# ACS_5_5.net
KiCad netlist of a schematic drawn in EAGLE
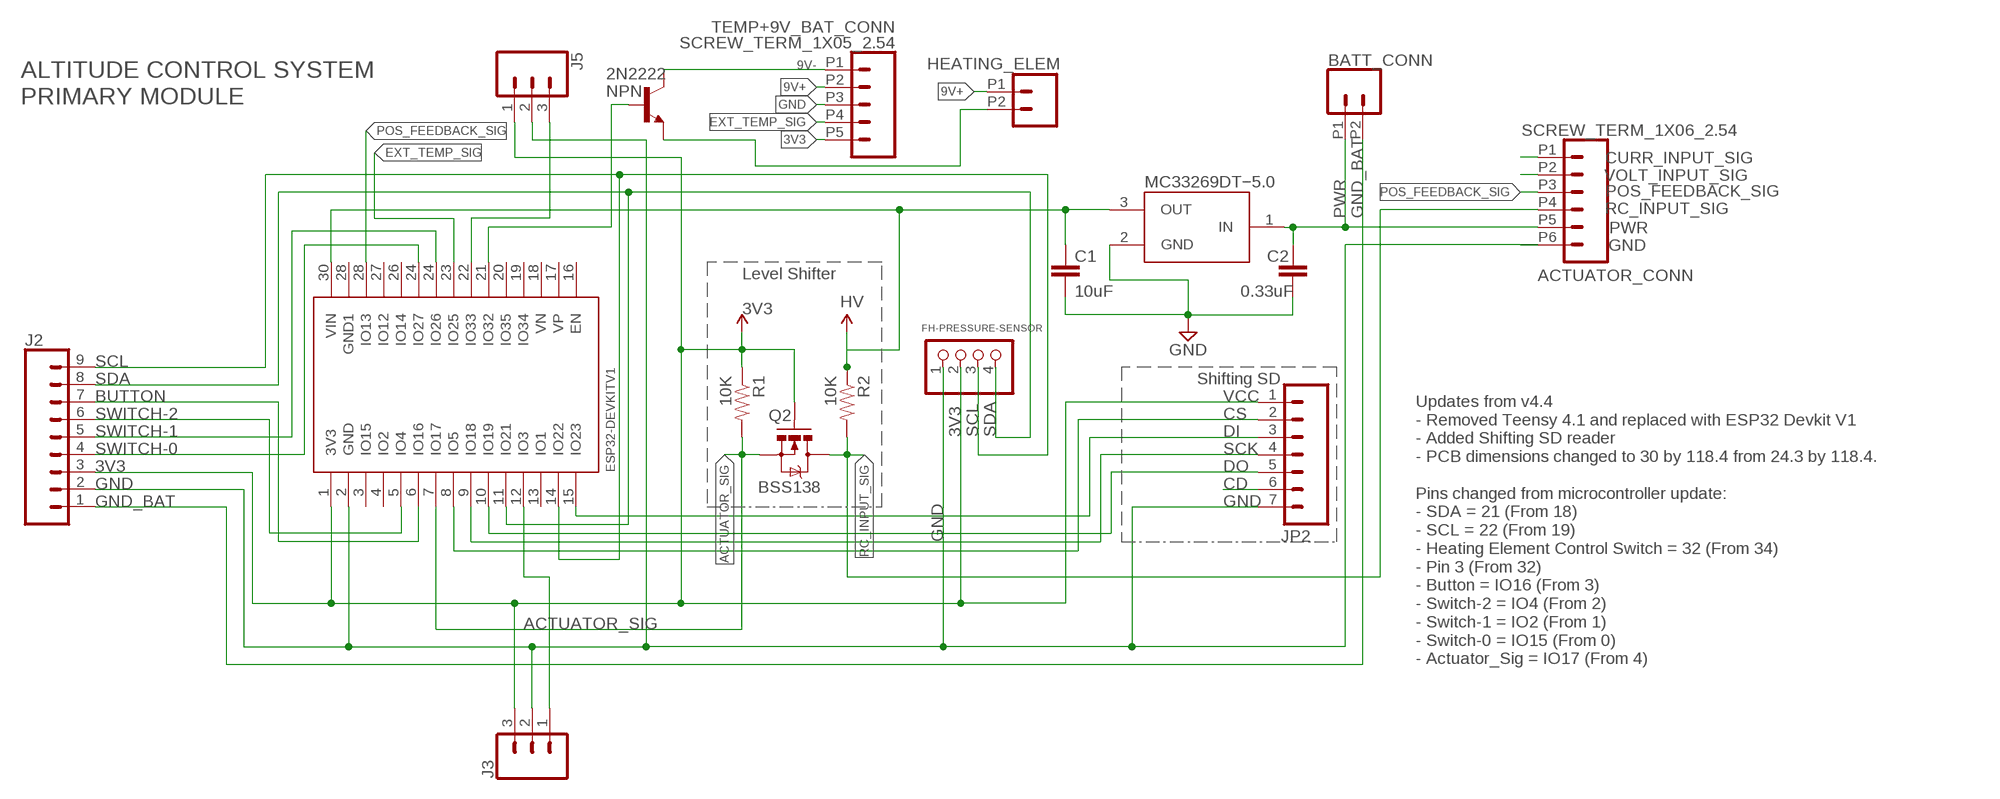
[diagram p0: schematic, sheet 1]

(export (version "E")
  (design (tool "Eeschema 10.0.6"))
  (components
    (comp (ref "2N2222")
      (value "NPN")
      (footprint "eagle-import:SOT95P237X112-3N")
      (libsource (lib "eagle-import") (part "NPNSOT23_"))
    )
    (comp (ref "ACTUATOR_CONN")
      (value "SCREW_TERM_1X06_2.54")
      (footprint "eagle-import:1X06_2.54_SCREWTERM")
      (libsource (lib "eagle-import") (part "SCREW_TERM_1X06_2.54"))
    )
    (comp (ref "BATT_CONN")
      (value "CONN_022.54MM_SCREWTERM")
      (footprint "eagle-import:1X02_2.54_SCREWTERM")
      (libsource (lib "eagle-import") (part "CONN_022.54MM_SCREWTERM"))
    )
    (comp (ref "C1")
      (value "10uF")
      (footprint "eagle-import:CAPC1608X85")
      (libsource (lib "eagle-import") (part "CCHIP-0603(1608-METRIC)_"))
    )
    (comp (ref "C2")
      (value "0.33uF")
      (footprint "eagle-import:CAPC1608X85")
      (libsource (lib "eagle-import") (part "CCHIP-0603(1608-METRIC)_"))
    )
    (comp (ref "FH-PRESSURE-SENSOR")
      (value "PINHD-1X4")
      (footprint "eagle-import:1X04")
      (libsource (lib "eagle-import") (part "PINHD-1X4"))
    )
    (comp (ref "HEATING_ELEM")
      (value "CONN_022.54MM_SCREWTERM")
      (footprint "eagle-import:1X02_2.54_SCREWTERM")
      (libsource (lib "eagle-import") (part "CONN_022.54MM_SCREWTERM"))
    )
    (comp (ref "J2")
      (value "CONN_09")
      (footprint "eagle-import:1X09")
      (libsource (lib "eagle-import") (part "CONN_09"))
    )
    (comp (ref "J3")
      (value "CONN_03")
      (footprint "eagle-import:1X03")
      (libsource (lib "eagle-import") (part "CONN_03"))
    )
    (comp (ref "J5")
      (value "CONN_03")
      (footprint "eagle-import:1X03")
      (libsource (lib "eagle-import") (part "CONN_03"))
    )
    (comp (ref "JP2")
      (value "M07")
      (footprint "eagle-import:1X07")
      (libsource (lib "eagle-import") (part "M07"))
    )
    (comp (ref "Q2")
      (value "BSS138")
      (footprint "eagle-import:SOT23-3")
      (libsource (lib "eagle-import") (part "MOSFET-NCHANNELSMD"))
    )
    (comp (ref "R1")
      (value "10K")
      (footprint "eagle-import:0603-RES")
      (libsource (lib "eagle-import") (part "RESISTOR0603-RES"))
    )
    (comp (ref "R2")
      (value "10K")
      (footprint "eagle-import:0603-RES")
      (libsource (lib "eagle-import") (part "RESISTOR0603-RES"))
    )
    (comp (ref "TEMP+9V_BAT_CONN")
      (value "SCREW_TERM_1X05_2.54")
      (footprint "eagle-import:1X05_2.54_SCREWTERM")
      (libsource (lib "eagle-import") (part "SCREW_TERM_1X05_2.54"))
    )
    (comp (ref "U$3")
      (value "ESP32DEVKITV1")
      (footprint "eagle-import:ESP32-DEVKITV1")
      (libsource (lib "eagle-import") (part "ESP32DEVKITV1"))
    )
    (comp (ref "U1")
      (value "MC78M05BDTRKG")
      (footprint "eagle-import:MC78M05BDTRKG")
      (fields
        (field (name "MANUFACTURER") "ON Semiconductor")
        (field (name "MPN") "IC REG LINEAR 5V 500MA DPAK")
        (field (name "CREATED_BY") "PCBLayout.com")
      )
      (libsource (lib "eagle-import") (part "MC78M05BDTRKG"))
    )
  )
  (nets
    (net (code "1") (name "/9V-") (class "Default")
      (node (ref "2N2222") (pin "3") (pinfunction "C_3") (pintype "passive"))
      (node (ref "TEMP+9V_BAT_CONN") (pin "P1") (pinfunction "1_P1") (pintype "passive"))
    )
    (net (code "2") (name "/BUTTON") (class "Default")
      (node (ref "J2") (pin "7") (pinfunction "7_7") (pintype "passive"))
      (node (ref "U$3") (pin "6") (pinfunction "IO16_6") (pintype "bidirectional"))
    )
    (net (code "3") (name "/CURR_INPUT_SIG") (class "Default")
      (node (ref "ACTUATOR_CONN") (pin "P1") (pinfunction "1_P1") (pintype "passive"))
    )
    (net (code "4") (name "/GND_BAT") (class "Default")
      (node (ref "BATT_CONN") (pin "P2") (pinfunction "2_P2") (pintype "passive"))
      (node (ref "J2") (pin "1") (pinfunction "1_1") (pintype "passive"))
    )
    (net (code "5") (name "/PWR") (class "Default")
      (node (ref "ACTUATOR_CONN") (pin "P5") (pinfunction "5_P5") (pintype "passive"))
      (node (ref "BATT_CONN") (pin "P1") (pinfunction "1_P1") (pintype "passive"))
      (node (ref "C2") (pin "1") (pinfunction "1_1") (pintype "passive"))
      (node (ref "U1") (pin "1") (pinfunction "IN_1") (pintype "input"))
    )
    (net (code "6") (name "/SCL") (class "Default")
      (node (ref "FH-PRESSURE-SENSOR") (pin "3") (pinfunction "3_3") (pintype "passive"))
      (node (ref "J2") (pin "9") (pinfunction "9_9") (pintype "passive"))
      (node (ref "U$3") (pin "14") (pinfunction "IO22_14") (pintype "bidirectional"))
    )
    (net (code "7") (name "/SDA") (class "Default")
      (node (ref "FH-PRESSURE-SENSOR") (pin "4") (pinfunction "4_4") (pintype "passive"))
      (node (ref "J2") (pin "8") (pinfunction "8_8") (pintype "passive"))
      (node (ref "U$3") (pin "11") (pinfunction "IO21_11") (pintype "bidirectional"))
    )
    (net (code "8") (name "/SWITCH-0") (class "Default")
      (node (ref "J2") (pin "4") (pinfunction "4_4") (pintype "passive"))
      (node (ref "U$3") (pin "24") (pinfunction "IO27_24") (pintype "bidirectional"))
    )
    (net (code "9") (name "/SWITCH-1") (class "Default")
      (node (ref "J2") (pin "5") (pinfunction "5_5") (pintype "passive"))
      (node (ref "U$3") (pin "24") (pinfunction "IO26_24") (pintype "bidirectional"))
    )
    (net (code "10") (name "/SWITCH-2") (class "Default")
      (node (ref "J2") (pin "6") (pinfunction "6_6") (pintype "passive"))
      (node (ref "U$3") (pin "5") (pinfunction "IO4_5") (pintype "bidirectional"))
    )
    (net (code "11") (name "/VOLT_INPUT_SIG") (class "Default")
      (node (ref "ACTUATOR_CONN") (pin "P2") (pinfunction "2_P2") (pintype "passive"))
    )
    (net (code "12") (name "3V3") (class "Default")
      (node (ref "FH-PRESSURE-SENSOR") (pin "2") (pinfunction "2_2") (pintype "passive"))
      (node (ref "J2") (pin "3") (pinfunction "3_3") (pintype "passive"))
      (node (ref "J3") (pin "3") (pinfunction "3_3") (pintype "passive"))
      (node (ref "J5") (pin "1") (pinfunction "1_1") (pintype "passive"))
      (node (ref "JP2") (pin "1") (pinfunction "1_1") (pintype "passive"))
      (node (ref "Q2") (pin "1") (pinfunction "G_1") (pintype "passive"))
      (node (ref "R1") (pin "1") (pinfunction "1_1") (pintype "passive"))
      (node (ref "TEMP+9V_BAT_CONN") (pin "P5") (pinfunction "5_P5") (pintype "passive"))
      (node (ref "U$3") (pin "1") (pinfunction "3V3_1") (pintype "bidirectional"))
    )
    (net (code "13") (name "9V+") (class "Default")
      (node (ref "HEATING_ELEM") (pin "P1") (pinfunction "1_P1") (pintype "passive"))
      (node (ref "TEMP+9V_BAT_CONN") (pin "P2") (pinfunction "2_P2") (pintype "passive"))
    )
    (net (code "14") (name "ACTUATOR_SIG") (class "Default")
      (node (ref "Q2") (pin "2") (pinfunction "S_2") (pintype "passive"))
      (node (ref "R1") (pin "2") (pinfunction "2_2") (pintype "passive"))
      (node (ref "U$3") (pin "7") (pinfunction "IO17_7") (pintype "bidirectional"))
    )
    (net (code "15") (name "EXT_TEMP_SIG") (class "Default")
      (node (ref "TEMP+9V_BAT_CONN") (pin "P4") (pinfunction "4_P4") (pintype "passive"))
      (node (ref "U$3") (pin "23") (pinfunction "IO25_23") (pintype "bidirectional"))
    )
    (net (code "16") (name "GND") (class "Default")
      (node (ref "ACTUATOR_CONN") (pin "P6") (pinfunction "6_P6") (pintype "passive"))
      (node (ref "C1") (pin "2") (pinfunction "2_2") (pintype "passive"))
      (node (ref "C2") (pin "2") (pinfunction "2_2") (pintype "passive"))
      (node (ref "FH-PRESSURE-SENSOR") (pin "1") (pinfunction "1_1") (pintype "passive"))
      (node (ref "J2") (pin "2") (pinfunction "2_2") (pintype "passive"))
      (node (ref "J3") (pin "2") (pinfunction "2_2") (pintype "passive"))
      (node (ref "J5") (pin "2") (pinfunction "2_2") (pintype "passive"))
      (node (ref "JP2") (pin "7") (pinfunction "7_7") (pintype "passive"))
      (node (ref "TEMP+9V_BAT_CONN") (pin "P3") (pinfunction "3_P3") (pintype "passive"))
      (node (ref "U$3") (pin "2") (pinfunction "GND_2") (pintype "bidirectional"))
      (node (ref "U1") (pin "2") (pinfunction "GND_2") (pintype "power_in"))
    )
    (net (code "17") (name "HV") (class "Default")
      (node (ref "C1") (pin "1") (pinfunction "1_1") (pintype "passive"))
      (node (ref "R2") (pin "1") (pinfunction "1_1") (pintype "passive"))
      (node (ref "U$3") (pin "30") (pinfunction "VIN_30") (pintype "bidirectional"))
      (node (ref "U1") (pin "3") (pinfunction "OUT_3") (pintype "output"))
    )
    (net (code "18") (name "Net-(2N2222-B)") (class "Default")
      (node (ref "2N2222") (pin "2") (pinfunction "B_2") (pintype "passive"))
      (node (ref "U$3") (pin "21") (pinfunction "IO32_21") (pintype "bidirectional"))
    )
    (net (code "19") (name "Net-(2N2222-E)") (class "Default")
      (node (ref "2N2222") (pin "1") (pinfunction "E_1") (pintype "passive"))
      (node (ref "HEATING_ELEM") (pin "P2") (pinfunction "2_P2") (pintype "passive"))
    )
    (net (code "20") (name "Net-(U$3-IO3)") (class "Default")
      (node (ref "J3") (pin "1") (pinfunction "1_1") (pintype "passive"))
      (node (ref "U$3") (pin "12") (pinfunction "IO3_12") (pintype "bidirectional"))
    )
    (net (code "21") (name "Net-(U$3-IO5)") (class "Default")
      (node (ref "JP2") (pin "2") (pinfunction "2_2") (pintype "passive"))
      (node (ref "U$3") (pin "8") (pinfunction "IO5_8") (pintype "bidirectional"))
    )
    (net (code "22") (name "Net-(U$3-IO18)") (class "Default")
      (node (ref "JP2") (pin "4") (pinfunction "4_4") (pintype "passive"))
      (node (ref "U$3") (pin "9") (pinfunction "IO18_9") (pintype "bidirectional"))
    )
    (net (code "23") (name "Net-(U$3-IO19)") (class "Default")
      (node (ref "JP2") (pin "5") (pinfunction "5_5") (pintype "passive"))
      (node (ref "U$3") (pin "10") (pinfunction "IO19_10") (pintype "bidirectional"))
    )
    (net (code "24") (name "Net-(U$3-IO23)") (class "Default")
      (node (ref "JP2") (pin "3") (pinfunction "3_3") (pintype "passive"))
      (node (ref "U$3") (pin "15") (pinfunction "IO23_15") (pintype "bidirectional"))
    )
    (net (code "25") (name "Net-(U$3-IO33)") (class "Default")
      (node (ref "J5") (pin "3") (pinfunction "3_3") (pintype "passive"))
      (node (ref "U$3") (pin "22") (pinfunction "IO33_22") (pintype "bidirectional"))
    )
    (net (code "26") (name "POS_FEEDBACK_SIG") (class "Default")
      (node (ref "ACTUATOR_CONN") (pin "P3") (pinfunction "3_P3") (pintype "passive"))
      (node (ref "U$3") (pin "28") (pinfunction "IO13_28") (pintype "bidirectional"))
    )
    (net (code "27") (name "RC_INPUT_SIG") (class "Default")
      (node (ref "ACTUATOR_CONN") (pin "P4") (pinfunction "4_P4") (pintype "passive"))
      (node (ref "Q2") (pin "3") (pinfunction "D_3") (pintype "passive"))
      (node (ref "R2") (pin "2") (pinfunction "2_2") (pintype "passive"))
    )
    (net (code "28") (name "unconnected-(JP2-Pad6)") (class "Default")
      (node (ref "JP2") (pin "6") (pinfunction "6_6") (pintype "passive"))
    )
    (net (code "29") (name "unconnected-(U$3-EN-Pad16)") (class "Default")
      (node (ref "U$3") (pin "16") (pinfunction "EN_16") (pintype "bidirectional"))
    )
    (net (code "30") (name "unconnected-(U$3-GND1-Pad28)") (class "Default")
      (node (ref "U$3") (pin "28") (pinfunction "GND1_28") (pintype "bidirectional"))
    )
    (net (code "31") (name "unconnected-(U$3-IO1-Pad13)") (class "Default")
      (node (ref "U$3") (pin "13") (pinfunction "IO1_13") (pintype "bidirectional"))
    )
    (net (code "32") (name "unconnected-(U$3-IO2-Pad4)") (class "Default")
      (node (ref "U$3") (pin "4") (pinfunction "IO2_4") (pintype "bidirectional"))
    )
    (net (code "33") (name "unconnected-(U$3-IO12-Pad27)") (class "Default")
      (node (ref "U$3") (pin "27") (pinfunction "IO12_27") (pintype "bidirectional"))
    )
    (net (code "34") (name "unconnected-(U$3-IO14-Pad26)") (class "Default")
      (node (ref "U$3") (pin "26") (pinfunction "IO14_26") (pintype "bidirectional"))
    )
    (net (code "35") (name "unconnected-(U$3-IO15-Pad3)") (class "Default")
      (node (ref "U$3") (pin "3") (pinfunction "IO15_3") (pintype "bidirectional"))
    )
    (net (code "36") (name "unconnected-(U$3-IO34-Pad19)") (class "Default")
      (node (ref "U$3") (pin "19") (pinfunction "IO34_19") (pintype "bidirectional"))
    )
    (net (code "37") (name "unconnected-(U$3-IO35-Pad20)") (class "Default")
      (node (ref "U$3") (pin "20") (pinfunction "IO35_20") (pintype "bidirectional"))
    )
    (net (code "38") (name "unconnected-(U$3-VN-Pad18)") (class "Default")
      (node (ref "U$3") (pin "18") (pinfunction "VN_18") (pintype "bidirectional"))
    )
    (net (code "39") (name "unconnected-(U$3-VP-Pad17)") (class "Default")
      (node (ref "U$3") (pin "17") (pinfunction "VP_17") (pintype "bidirectional"))
    )
  )
)
